# H_Bridge.net
KiCad netlist of a schematic drawn in Altium Designer
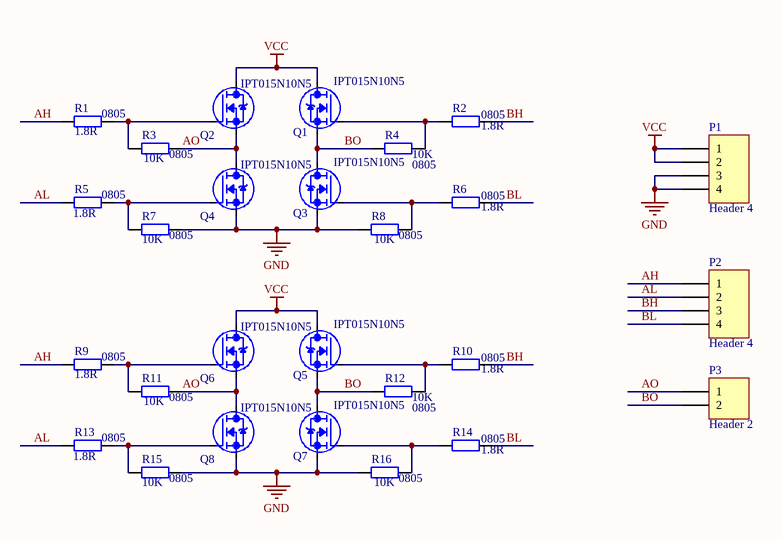
[diagram p0: H_Bridge.SchDoc]

(export (version "E")
  (design (tool "Eeschema 10.0.6"))
  (components
    (comp (ref "P1")
      (value "Header 4")
      (footprint "HDR2.54-LI-4P")
      (description "Header, 4-Pin")
      (fields (field (name "PUBLISHER") "Altium Limited"))
      (libsource (lib "QT") (part "Header 4"))
    )
    (comp (ref "P2")
      (value "Header 4")
      (footprint "HDR2.54-LI-4P")
      (description "Header, 4-Pin")
      (fields (field (name "PUBLISHER") "Altium Limited"))
      (libsource (lib "QT") (part "Header 4"))
    )
    (comp (ref "P3")
      (value "Header 2")
      (footprint "HDR2.54-LI-2P")
      (description "Header, 2-Pin")
      (fields (field (name "PUBLISHER") "Altium Limited"))
      (libsource (lib "QT") (part "Header 2"))
    )
    (comp (ref "Q1")
      (value "IPT015N10N5")
      (footprint "HSOF-8")
      (libsource (lib "常用元件库") (part "NMOS-HSOF-8"))
    )
    (comp (ref "Q2")
      (value "IPT015N10N5")
      (footprint "HSOF-8")
      (libsource (lib "常用元件库") (part "NMOS-HSOF-8"))
    )
    (comp (ref "Q3")
      (value "IPT015N10N5")
      (footprint "HSOF-8")
      (libsource (lib "常用元件库") (part "NMOS-HSOF-8"))
    )
    (comp (ref "Q4")
      (value "IPT015N10N5")
      (footprint "HSOF-8")
      (libsource (lib "常用元件库") (part "NMOS-HSOF-8"))
    )
    (comp (ref "Q5")
      (value "IPT015N10N5")
      (footprint "HSOF-8")
      (libsource (lib "常用元件库") (part "NMOS-HSOF-8"))
    )
    (comp (ref "Q6")
      (value "IPT015N10N5")
      (footprint "HSOF-8")
      (libsource (lib "常用元件库") (part "NMOS-HSOF-8"))
    )
    (comp (ref "Q7")
      (value "IPT015N10N5")
      (footprint "HSOF-8")
      (libsource (lib "常用元件库") (part "NMOS-HSOF-8"))
    )
    (comp (ref "Q8")
      (value "IPT015N10N5")
      (footprint "HSOF-8")
      (libsource (lib "常用元件库") (part "NMOS-HSOF-8"))
    )
    (comp (ref "R1")
      (value "0805")
      (footprint "R 0805_L")
      (description "Resistor")
      (fields (field (name "ALTIUM_VALUE") "1.8R") (field (name "PUBLISHER") "Altium Limited"))
      (libsource (lib "QT") (part "RES2"))
    )
    (comp (ref "R2")
      (value "0805")
      (footprint "R 0805_L")
      (description "Resistor")
      (fields (field (name "ALTIUM_VALUE") "1.8R") (field (name "PUBLISHER") "Altium Limited"))
      (libsource (lib "QT") (part "RES2"))
    )
    (comp (ref "R3")
      (value "0805")
      (footprint "R 0805_L")
      (description "Resistor")
      (fields (field (name "ALTIUM_VALUE") "10K") (field (name "PUBLISHER") "Altium Limited"))
      (libsource (lib "QT") (part "RES2"))
    )
    (comp (ref "R4")
      (value "0805")
      (footprint "R 0805_L")
      (description "Resistor")
      (fields (field (name "ALTIUM_VALUE") "10K") (field (name "PUBLISHER") "Altium Limited"))
      (libsource (lib "QT") (part "RES2"))
    )
    (comp (ref "R5")
      (value "0805")
      (footprint "R 0805_L")
      (description "Resistor")
      (fields (field (name "ALTIUM_VALUE") "1.8R") (field (name "PUBLISHER") "Altium Limited"))
      (libsource (lib "QT") (part "RES2"))
    )
    (comp (ref "R6")
      (value "0805")
      (footprint "R 0805_L")
      (description "Resistor")
      (fields (field (name "ALTIUM_VALUE") "1.8R") (field (name "PUBLISHER") "Altium Limited"))
      (libsource (lib "QT") (part "RES2"))
    )
    (comp (ref "R7")
      (value "0805")
      (footprint "R 0805_L")
      (description "Resistor")
      (fields (field (name "ALTIUM_VALUE") "10K") (field (name "PUBLISHER") "Altium Limited"))
      (libsource (lib "QT") (part "RES2"))
    )
    (comp (ref "R8")
      (value "0805")
      (footprint "R 0805_L")
      (description "Resistor")
      (fields (field (name "ALTIUM_VALUE") "10K") (field (name "PUBLISHER") "Altium Limited"))
      (libsource (lib "QT") (part "RES2"))
    )
    (comp (ref "R9")
      (value "0805")
      (footprint "R 0805_L")
      (description "Resistor")
      (fields (field (name "ALTIUM_VALUE") "1.8R") (field (name "PUBLISHER") "Altium Limited"))
      (libsource (lib "QT") (part "RES2"))
    )
    (comp (ref "R10")
      (value "0805")
      (footprint "R 0805_L")
      (description "Resistor")
      (fields (field (name "ALTIUM_VALUE") "1.8R") (field (name "PUBLISHER") "Altium Limited"))
      (libsource (lib "QT") (part "RES2"))
    )
    (comp (ref "R11")
      (value "0805")
      (footprint "R 0805_L")
      (description "Resistor")
      (fields (field (name "ALTIUM_VALUE") "10K") (field (name "PUBLISHER") "Altium Limited"))
      (libsource (lib "QT") (part "RES2"))
    )
    (comp (ref "R12")
      (value "0805")
      (footprint "R 0805_L")
      (description "Resistor")
      (fields (field (name "ALTIUM_VALUE") "10K") (field (name "PUBLISHER") "Altium Limited"))
      (libsource (lib "QT") (part "RES2"))
    )
    (comp (ref "R13")
      (value "0805")
      (footprint "R 0805_L")
      (description "Resistor")
      (fields (field (name "ALTIUM_VALUE") "1.8R") (field (name "PUBLISHER") "Altium Limited"))
      (libsource (lib "QT") (part "RES2"))
    )
    (comp (ref "R14")
      (value "0805")
      (footprint "R 0805_L")
      (description "Resistor")
      (fields (field (name "ALTIUM_VALUE") "1.8R") (field (name "PUBLISHER") "Altium Limited"))
      (libsource (lib "QT") (part "RES2"))
    )
    (comp (ref "R15")
      (value "0805")
      (footprint "R 0805_L")
      (description "Resistor")
      (fields (field (name "ALTIUM_VALUE") "10K") (field (name "PUBLISHER") "Altium Limited"))
      (libsource (lib "QT") (part "RES2"))
    )
    (comp (ref "R16")
      (value "0805")
      (footprint "R 0805_L")
      (description "Resistor")
      (fields (field (name "ALTIUM_VALUE") "10K") (field (name "PUBLISHER") "Altium Limited"))
      (libsource (lib "QT") (part "RES2"))
    )
  )
  (nets
    (net (code "1") (name "/AH") (class "Default")
      (node (ref "P2") (pin "1") (pinfunction "1_1") (pintype "passive"))
      (node (ref "R1") (pin "1") (pinfunction "1_1") (pintype "passive"))
      (node (ref "R9") (pin "1") (pinfunction "1_1") (pintype "passive"))
    )
    (net (code "2") (name "/AL") (class "Default")
      (node (ref "P2") (pin "2") (pinfunction "2_2") (pintype "passive"))
      (node (ref "R13") (pin "1") (pinfunction "1_1") (pintype "passive"))
      (node (ref "R5") (pin "1") (pinfunction "1_1") (pintype "passive"))
    )
    (net (code "3") (name "/AO") (class "Default")
      (node (ref "P3") (pin "1") (pinfunction "1_1") (pintype "passive"))
      (node (ref "Q2") (pin "2-8") (pinfunction "S_2-8") (pintype "passive"))
      (node (ref "Q4") (pin "9") (pinfunction "D_9") (pintype "passive"))
      (node (ref "Q6") (pin "2-8") (pinfunction "S_2-8") (pintype "passive"))
      (node (ref "Q8") (pin "9") (pinfunction "D_9") (pintype "passive"))
      (node (ref "R11") (pin "2") (pinfunction "2_2") (pintype "passive"))
      (node (ref "R3") (pin "2") (pinfunction "2_2") (pintype "passive"))
    )
    (net (code "4") (name "/BH") (class "Default")
      (node (ref "P2") (pin "3") (pinfunction "3_3") (pintype "passive"))
      (node (ref "R10") (pin "2") (pinfunction "2_2") (pintype "passive"))
      (node (ref "R2") (pin "2") (pinfunction "2_2") (pintype "passive"))
    )
    (net (code "5") (name "/BL") (class "Default")
      (node (ref "P2") (pin "4") (pinfunction "4_4") (pintype "passive"))
      (node (ref "R14") (pin "2") (pinfunction "2_2") (pintype "passive"))
      (node (ref "R6") (pin "2") (pinfunction "2_2") (pintype "passive"))
    )
    (net (code "6") (name "/BO") (class "Default")
      (node (ref "P3") (pin "2") (pinfunction "2_2") (pintype "passive"))
      (node (ref "Q1") (pin "2-8") (pinfunction "S_2-8") (pintype "passive"))
      (node (ref "Q3") (pin "9") (pinfunction "D_9") (pintype "passive"))
      (node (ref "Q5") (pin "2-8") (pinfunction "S_2-8") (pintype "passive"))
      (node (ref "Q7") (pin "9") (pinfunction "D_9") (pintype "passive"))
      (node (ref "R12") (pin "1") (pinfunction "1_1") (pintype "passive"))
      (node (ref "R4") (pin "1") (pinfunction "1_1") (pintype "passive"))
    )
    (net (code "7") (name "GND") (class "Default")
      (node (ref "P1") (pin "3") (pinfunction "3_3") (pintype "passive"))
      (node (ref "P1") (pin "4") (pinfunction "4_4") (pintype "passive"))
      (node (ref "Q3") (pin "2-8") (pinfunction "S_2-8") (pintype "passive"))
      (node (ref "Q4") (pin "2-8") (pinfunction "S_2-8") (pintype "passive"))
      (node (ref "Q7") (pin "2-8") (pinfunction "S_2-8") (pintype "passive"))
      (node (ref "Q8") (pin "2-8") (pinfunction "S_2-8") (pintype "passive"))
      (node (ref "R15") (pin "2") (pinfunction "2_2") (pintype "passive"))
      (node (ref "R16") (pin "1") (pinfunction "1_1") (pintype "passive"))
      (node (ref "R7") (pin "2") (pinfunction "2_2") (pintype "passive"))
      (node (ref "R8") (pin "1") (pinfunction "1_1") (pintype "passive"))
    )
    (net (code "8") (name "Net-(Q1-G)") (class "Default")
      (node (ref "Q1") (pin "1") (pinfunction "G_1") (pintype "passive"))
      (node (ref "R2") (pin "1") (pinfunction "1_1") (pintype "passive"))
      (node (ref "R4") (pin "2") (pinfunction "2_2") (pintype "passive"))
    )
    (net (code "9") (name "Net-(Q2-G)") (class "Default")
      (node (ref "Q2") (pin "1") (pinfunction "G_1") (pintype "passive"))
      (node (ref "R1") (pin "2") (pinfunction "2_2") (pintype "passive"))
      (node (ref "R3") (pin "1") (pinfunction "1_1") (pintype "passive"))
    )
    (net (code "10") (name "Net-(Q3-G)") (class "Default")
      (node (ref "Q3") (pin "1") (pinfunction "G_1") (pintype "passive"))
      (node (ref "R6") (pin "1") (pinfunction "1_1") (pintype "passive"))
      (node (ref "R8") (pin "2") (pinfunction "2_2") (pintype "passive"))
    )
    (net (code "11") (name "Net-(Q4-G)") (class "Default")
      (node (ref "Q4") (pin "1") (pinfunction "G_1") (pintype "passive"))
      (node (ref "R5") (pin "2") (pinfunction "2_2") (pintype "passive"))
      (node (ref "R7") (pin "1") (pinfunction "1_1") (pintype "passive"))
    )
    (net (code "12") (name "Net-(Q5-G)") (class "Default")
      (node (ref "Q5") (pin "1") (pinfunction "G_1") (pintype "passive"))
      (node (ref "R10") (pin "1") (pinfunction "1_1") (pintype "passive"))
      (node (ref "R12") (pin "2") (pinfunction "2_2") (pintype "passive"))
    )
    (net (code "13") (name "Net-(Q6-G)") (class "Default")
      (node (ref "Q6") (pin "1") (pinfunction "G_1") (pintype "passive"))
      (node (ref "R11") (pin "1") (pinfunction "1_1") (pintype "passive"))
      (node (ref "R9") (pin "2") (pinfunction "2_2") (pintype "passive"))
    )
    (net (code "14") (name "Net-(Q7-G)") (class "Default")
      (node (ref "Q7") (pin "1") (pinfunction "G_1") (pintype "passive"))
      (node (ref "R14") (pin "1") (pinfunction "1_1") (pintype "passive"))
      (node (ref "R16") (pin "2") (pinfunction "2_2") (pintype "passive"))
    )
    (net (code "15") (name "Net-(Q8-G)") (class "Default")
      (node (ref "Q8") (pin "1") (pinfunction "G_1") (pintype "passive"))
      (node (ref "R13") (pin "2") (pinfunction "2_2") (pintype "passive"))
      (node (ref "R15") (pin "1") (pinfunction "1_1") (pintype "passive"))
    )
    (net (code "16") (name "VCC") (class "Default")
      (node (ref "P1") (pin "1") (pinfunction "1_1") (pintype "passive"))
      (node (ref "P1") (pin "2") (pinfunction "2_2") (pintype "passive"))
      (node (ref "Q1") (pin "9") (pinfunction "D_9") (pintype "passive"))
      (node (ref "Q2") (pin "9") (pinfunction "D_9") (pintype "passive"))
      (node (ref "Q5") (pin "9") (pinfunction "D_9") (pintype "passive"))
      (node (ref "Q6") (pin "9") (pinfunction "D_9") (pintype "passive"))
    )
  )
)
